# Feather-M0-RAK811-UFL.net
KiCad netlist of a schematic drawn in EAGLE
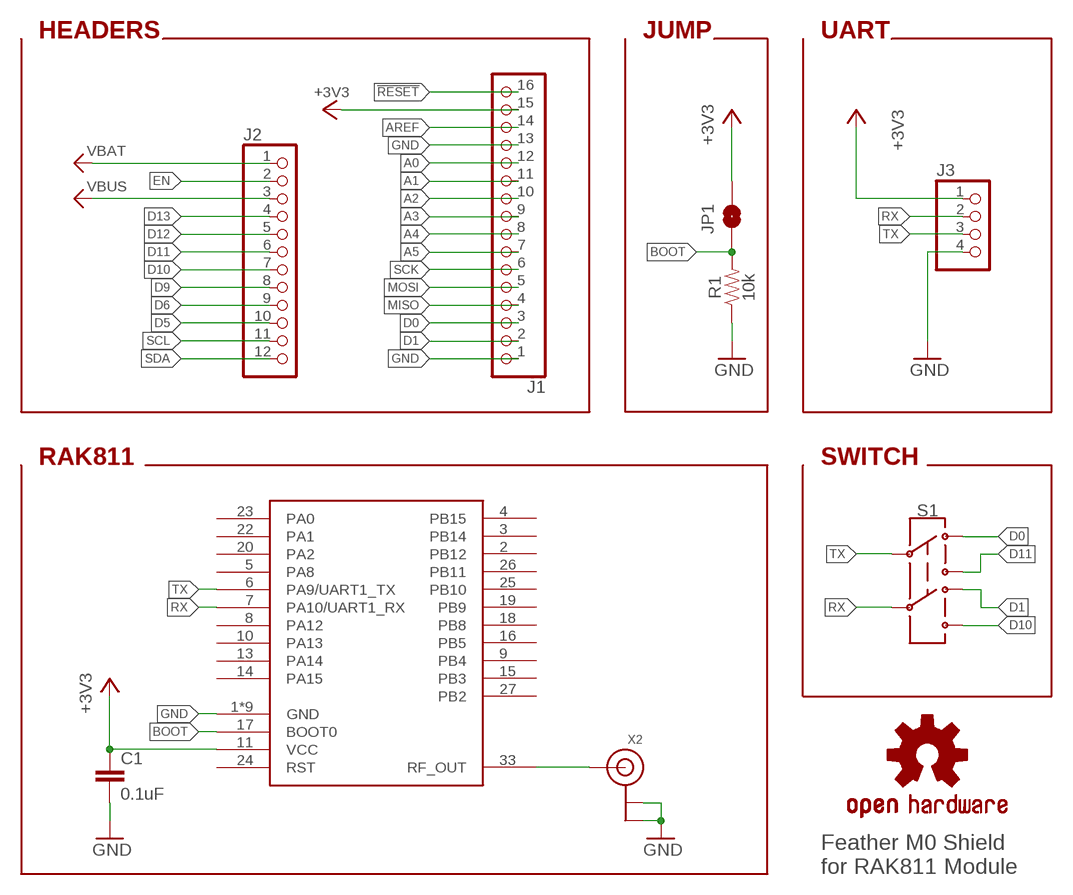
[diagram p0: schematic, sheet 1]

(export (version "E")
  (design (tool "Eeschema 10.0.6"))
  (components
    (comp (ref "C1")
      (value "0.1uF")
      (footprint "eagle-import:0603")
      (libsource (lib "eagle-import") (part "0.1UF-0603-25V-(+80/-20%)"))
    )
    (comp (ref "J1")
      (value "HEADER-1X16ROUND")
      (footprint "eagle-import:1X16_ROUND")
      (libsource (lib "eagle-import") (part "HEADER-1X16ROUND"))
    )
    (comp (ref "J2")
      (value "HEADER-1X12")
      (footprint "eagle-import:1X12_ROUND")
      (libsource (lib "eagle-import") (part "HEADER-1X12"))
    )
    (comp (ref "J3")
      (value "HEADER-1X4ROUND")
      (footprint "eagle-import:1X04_ROUND")
      (libsource (lib "eagle-import") (part "HEADER-1X4ROUND"))
    )
    (comp (ref "JP1")
      (value "JUMPER-SMT_2_NO_SILK")
      (footprint "eagle-import:SMT-JUMPER_2_NO_SILK")
      (libsource (lib "eagle-import") (part "JUMPER-SMT_2_NO_SILK"))
    )
    (comp (ref "LOGO1")
      (value "OSHW-LOGOS")
      (footprint "eagle-import:OSHW-LOGO-S")
      (libsource (lib "eagle-import") (part "OSHW-LOGOS"))
    )
    (comp (ref "R1")
      (value "10k")
      (footprint "eagle-import:0603")
      (libsource (lib "eagle-import") (part "10KOHM-0603-1/10W-1%"))
    )
    (comp (ref "S1")
      (value "SWITCH-DPDT-SMD-AYZ0202")
      (footprint "eagle-import:SWITCH_DPDT_SMD_AYZ0202")
      (libsource (lib "eagle-import") (part "SWITCH-DPDT-SMD-AYZ0202"))
    )
    (comp (ref "U1")
      (value "RAK_WIRELESS_RAK811")
      (footprint "eagle-import:RAK_WIRELESS_RAK811")
      (libsource (lib "eagle-import") (part "RAK_WIRELESS_RAK811"))
    )
    (comp (ref "X2")
      (value "ANTENNA_U.FL")
      (footprint "eagle-import:U.FL")
      (libsource (lib "eagle-import") (part "ANTENNA_U.FL"))
    )
  )
  (nets
    (net (code "1") (name "+3V3") (class "Default")
      (node (ref "C1") (pin "1") (pinfunction "1_1") (pintype "passive"))
      (node (ref "J1") (pin "15") (pinfunction "15_15") (pintype "passive"))
      (node (ref "J3") (pin "1") (pinfunction "1_1") (pintype "passive"))
      (node (ref "JP1") (pin "2") (pinfunction "2_2") (pintype "passive"))
      (node (ref "U1") (pin "11") (pinfunction "VCC_11") (pintype "power_in"))
    )
    (net (code "2") (name "/~{RESET}") (class "Default")
      (node (ref "J1") (pin "16") (pinfunction "16_16") (pintype "passive"))
    )
    (net (code "3") (name "A0") (class "Default")
      (node (ref "J1") (pin "12") (pinfunction "12_12") (pintype "passive"))
    )
    (net (code "4") (name "A1") (class "Default")
      (node (ref "J1") (pin "11") (pinfunction "11_11") (pintype "passive"))
    )
    (net (code "5") (name "A2") (class "Default")
      (node (ref "J1") (pin "10") (pinfunction "10_10") (pintype "passive"))
    )
    (net (code "6") (name "A3") (class "Default")
      (node (ref "J1") (pin "9") (pinfunction "9_9") (pintype "passive"))
    )
    (net (code "7") (name "A4") (class "Default")
      (node (ref "J1") (pin "8") (pinfunction "8_8") (pintype "passive"))
    )
    (net (code "8") (name "A5") (class "Default")
      (node (ref "J1") (pin "7") (pinfunction "7_7") (pintype "passive"))
    )
    (net (code "9") (name "AREF") (class "Default")
      (node (ref "J1") (pin "14") (pinfunction "14_14") (pintype "passive"))
    )
    (net (code "10") (name "BOOT") (class "Default")
      (node (ref "JP1") (pin "1") (pinfunction "1_1") (pintype "passive"))
      (node (ref "R1") (pin "2") (pinfunction "2_2") (pintype "passive"))
      (node (ref "U1") (pin "17") (pinfunction "BOOT0_17") (pintype "input"))
    )
    (net (code "11") (name "D0") (class "Default")
      (node (ref "J1") (pin "3") (pinfunction "3_3") (pintype "passive"))
      (node (ref "S1") (pin "1") (pinfunction "1_1") (pintype "bidirectional"))
    )
    (net (code "12") (name "D1") (class "Default")
      (node (ref "J1") (pin "2") (pinfunction "2_2") (pintype "passive"))
      (node (ref "S1") (pin "4") (pinfunction "4_4") (pintype "bidirectional"))
    )
    (net (code "13") (name "D5") (class "Default")
      (node (ref "J2") (pin "10") (pinfunction "10_10") (pintype "passive"))
    )
    (net (code "14") (name "D6") (class "Default")
      (node (ref "J2") (pin "9") (pinfunction "9_9") (pintype "passive"))
    )
    (net (code "15") (name "D9") (class "Default")
      (node (ref "J2") (pin "8") (pinfunction "8_8") (pintype "passive"))
    )
    (net (code "16") (name "D10") (class "Default")
      (node (ref "J2") (pin "7") (pinfunction "7_7") (pintype "passive"))
      (node (ref "S1") (pin "6") (pinfunction "6_6") (pintype "bidirectional"))
    )
    (net (code "17") (name "D11") (class "Default")
      (node (ref "J2") (pin "6") (pinfunction "6_6") (pintype "passive"))
      (node (ref "S1") (pin "3") (pinfunction "3_3") (pintype "bidirectional"))
    )
    (net (code "18") (name "D12") (class "Default")
      (node (ref "J2") (pin "5") (pinfunction "5_5") (pintype "passive"))
    )
    (net (code "19") (name "D13") (class "Default")
      (node (ref "J2") (pin "4") (pinfunction "4_4") (pintype "passive"))
    )
    (net (code "20") (name "EN") (class "Default")
      (node (ref "J2") (pin "2") (pinfunction "2_2") (pintype "passive"))
    )
    (net (code "21") (name "GND") (class "Default")
      (node (ref "C1") (pin "2") (pinfunction "2_2") (pintype "passive"))
      (node (ref "J1") (pin "1") (pinfunction "1_1") (pintype "passive"))
      (node (ref "J1") (pin "13") (pinfunction "13_13") (pintype "passive"))
      (node (ref "J3") (pin "4") (pinfunction "4_4") (pintype "passive"))
      (node (ref "R1") (pin "1") (pinfunction "1_1") (pintype "passive"))
      (node (ref "U1") (pin "1") (pinfunction "GND_1") (pintype "power_in"))
      (node (ref "U1") (pin "12") (pinfunction "GND_12") (pintype "power_in"))
      (node (ref "U1") (pin "21") (pinfunction "GND_21") (pintype "power_in"))
      (node (ref "U1") (pin "28") (pinfunction "GND_28") (pintype "power_in"))
      (node (ref "U1") (pin "29") (pinfunction "GND_29") (pintype "power_in"))
      (node (ref "U1") (pin "30") (pinfunction "GND_30") (pintype "power_in"))
      (node (ref "U1") (pin "31") (pinfunction "GND_31") (pintype "power_in"))
      (node (ref "U1") (pin "32") (pinfunction "GND_32") (pintype "power_in"))
      (node (ref "U1") (pin "34") (pinfunction "GND_34") (pintype "power_in"))
      (node (ref "X2") (pin "1") (pinfunction "GND_1") (pintype "passive"))
      (node (ref "X2") (pin "2") (pinfunction "GND_2") (pintype "passive"))
    )
    (net (code "22") (name "MISO") (class "Default")
      (node (ref "J1") (pin "4") (pinfunction "4_4") (pintype "passive"))
    )
    (net (code "23") (name "MOSI") (class "Default")
      (node (ref "J1") (pin "5") (pinfunction "5_5") (pintype "passive"))
    )
    (net (code "24") (name "Net-(U1-RF_OUT)") (class "Default")
      (node (ref "U1") (pin "33") (pinfunction "RF_OUT_33") (pintype "bidirectional"))
      (node (ref "X2") (pin "3") (pinfunction "SIGNAL_3") (pintype "passive"))
    )
    (net (code "25") (name "RX") (class "Default")
      (node (ref "J3") (pin "2") (pinfunction "2_2") (pintype "passive"))
      (node (ref "S1") (pin "5") (pinfunction "5_5") (pintype "bidirectional"))
      (node (ref "U1") (pin "7") (pinfunction "PA10/UART1_RX_7") (pintype "input"))
    )
    (net (code "26") (name "SCK") (class "Default")
      (node (ref "J1") (pin "6") (pinfunction "6_6") (pintype "passive"))
    )
    (net (code "27") (name "SCL") (class "Default")
      (node (ref "J2") (pin "11") (pinfunction "11_11") (pintype "passive"))
    )
    (net (code "28") (name "SDA") (class "Default")
      (node (ref "J2") (pin "12") (pinfunction "12_12") (pintype "passive"))
    )
    (net (code "29") (name "TX") (class "Default")
      (node (ref "J3") (pin "3") (pinfunction "3_3") (pintype "passive"))
      (node (ref "S1") (pin "2") (pinfunction "2_2") (pintype "bidirectional"))
      (node (ref "U1") (pin "6") (pinfunction "PA9/UART1_TX_6") (pintype "bidirectional"))
    )
    (net (code "30") (name "VBAT") (class "Default")
      (node (ref "J2") (pin "1") (pinfunction "1_1") (pintype "passive"))
    )
    (net (code "31") (name "VBUS") (class "Default")
      (node (ref "J2") (pin "3") (pinfunction "3_3") (pintype "passive"))
    )
    (net (code "32") (name "unconnected-(U1-PA0-Pad23)") (class "Default")
      (node (ref "U1") (pin "23") (pinfunction "PA0_23") (pintype "bidirectional"))
    )
    (net (code "33") (name "unconnected-(U1-PA1-Pad22)") (class "Default")
      (node (ref "U1") (pin "22") (pinfunction "PA1_22") (pintype "input"))
    )
    (net (code "34") (name "unconnected-(U1-PA2-Pad20)") (class "Default")
      (node (ref "U1") (pin "20") (pinfunction "PA2_20") (pintype "bidirectional"))
    )
    (net (code "35") (name "unconnected-(U1-PA8-Pad5)") (class "Default")
      (node (ref "U1") (pin "5") (pinfunction "PA8_5") (pintype "bidirectional"))
    )
    (net (code "36") (name "unconnected-(U1-PA12-Pad8)") (class "Default")
      (node (ref "U1") (pin "8") (pinfunction "PA12_8") (pintype "bidirectional"))
    )
    (net (code "37") (name "unconnected-(U1-PA13-Pad10)") (class "Default")
      (node (ref "U1") (pin "10") (pinfunction "PA13_10") (pintype "bidirectional"))
    )
    (net (code "38") (name "unconnected-(U1-PA14-Pad13)") (class "Default")
      (node (ref "U1") (pin "13") (pinfunction "PA14_13") (pintype "bidirectional"))
    )
    (net (code "39") (name "unconnected-(U1-PA15-Pad14)") (class "Default")
      (node (ref "U1") (pin "14") (pinfunction "PA15_14") (pintype "bidirectional"))
    )
    (net (code "40") (name "unconnected-(U1-PB2-Pad27)") (class "Default")
      (node (ref "U1") (pin "27") (pinfunction "PB2_27") (pintype "bidirectional"))
    )
    (net (code "41") (name "unconnected-(U1-PB3-Pad15)") (class "Default")
      (node (ref "U1") (pin "15") (pinfunction "PB3_15") (pintype "bidirectional"))
    )
    (net (code "42") (name "unconnected-(U1-PB4-Pad9)") (class "Default")
      (node (ref "U1") (pin "9") (pinfunction "PB4_9") (pintype "input"))
    )
    (net (code "43") (name "unconnected-(U1-PB5-Pad16)") (class "Default")
      (node (ref "U1") (pin "16") (pinfunction "PB5_16") (pintype "bidirectional"))
    )
    (net (code "44") (name "unconnected-(U1-PB8-Pad18)") (class "Default")
      (node (ref "U1") (pin "18") (pinfunction "PB8_18") (pintype "bidirectional"))
    )
    (net (code "45") (name "unconnected-(U1-PB9-Pad19)") (class "Default")
      (node (ref "U1") (pin "19") (pinfunction "PB9_19") (pintype "bidirectional"))
    )
    (net (code "46") (name "unconnected-(U1-PB10-Pad25)") (class "Default")
      (node (ref "U1") (pin "25") (pinfunction "PB10_25") (pintype "bidirectional"))
    )
    (net (code "47") (name "unconnected-(U1-PB11-Pad26)") (class "Default")
      (node (ref "U1") (pin "26") (pinfunction "PB11_26") (pintype "bidirectional"))
    )
    (net (code "48") (name "unconnected-(U1-PB12-Pad2)") (class "Default")
      (node (ref "U1") (pin "2") (pinfunction "PB12_2") (pintype "bidirectional"))
    )
    (net (code "49") (name "unconnected-(U1-PB14-Pad3)") (class "Default")
      (node (ref "U1") (pin "3") (pinfunction "PB14_3") (pintype "bidirectional"))
    )
    (net (code "50") (name "unconnected-(U1-PB15-Pad4)") (class "Default")
      (node (ref "U1") (pin "4") (pinfunction "PB15_4") (pintype "bidirectional"))
    )
    (net (code "51") (name "unconnected-(U1-RST-Pad24)") (class "Default")
      (node (ref "U1") (pin "24") (pinfunction "RST_24") (pintype "input"))
    )
  )
)
